# SCH_LD_project_2022-11-01.net
KiCad netlist of a schematic drawn in EasyEDA
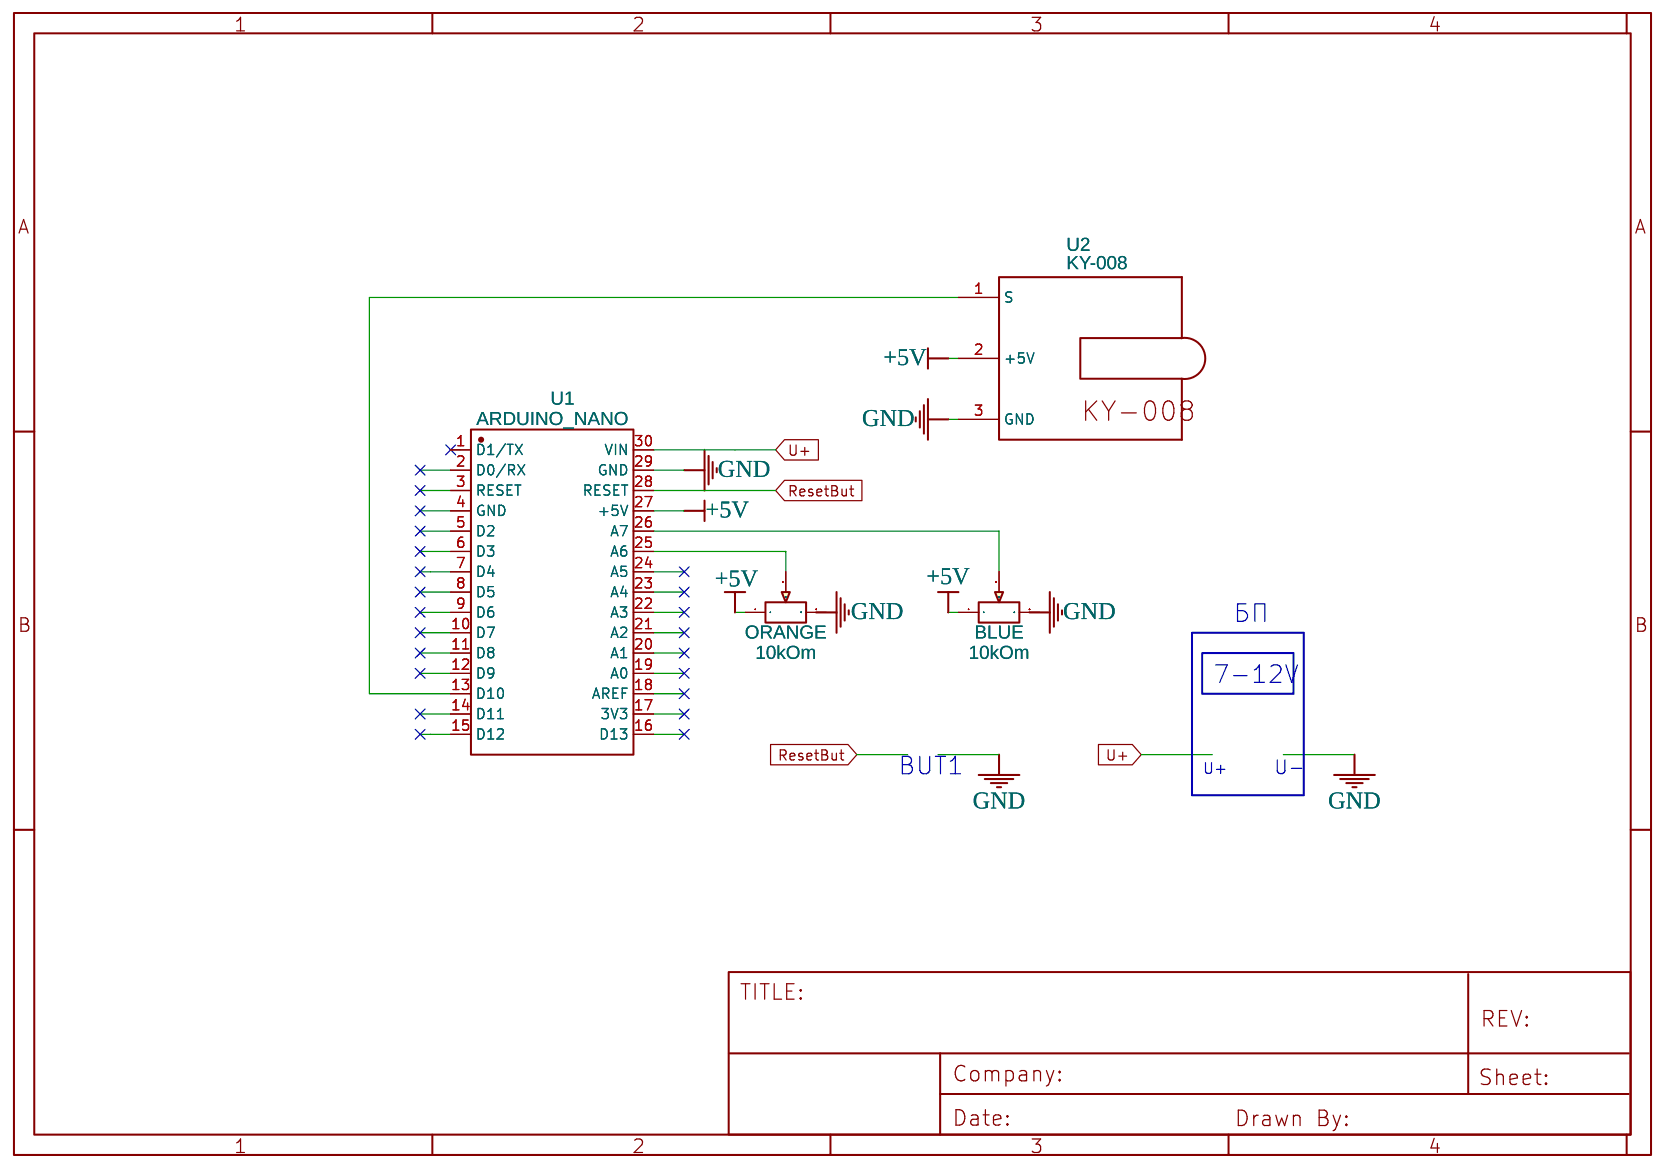
[diagram p0: schematic sheet]

(export (version "E")
  (design (tool "Eeschema 10.0.6"))
  (components
    (comp (ref "BLUE") (value "10kOm") (libsource (lib "") (part "R_3386P_EU")))
    (comp (ref "ORANGE") (value "10kOm") (libsource (lib "") (part "R_3386P_EU_1")))
    (comp (ref "U1")
      (value "ARDUINO_NANO")
      (fields (field (name "BOM_Supplier Part") "C9900017879"))
      (libsource (lib "") (part "ARDUINO_NANO"))
    )
    (comp (ref "U2") (value "KY-008") (libsource (lib "") (part "KY-008")))
  )
  (nets
    (net (code "1") (name "+5V") (class "Default")
      (node (ref "BLUE") (pin "1") (pinfunction "1_1") (pintype "input"))
      (node (ref "ORANGE") (pin "1") (pinfunction "1_1") (pintype "input"))
      (node (ref "U1") (pin "27") (pinfunction "+5V_27") (pintype "unspecified"))
      (node (ref "U2") (pin "2") (pinfunction "+5V_2") (pintype "unspecified"))
    )
    (net (code "2") (name "GND") (class "Default")
      (node (ref "BLUE") (pin "3") (pinfunction "3_3") (pintype "input"))
      (node (ref "ORANGE") (pin "3") (pinfunction "3_3") (pintype "input"))
      (node (ref "U1") (pin "29") (pinfunction "GND_29") (pintype "unspecified"))
      (node (ref "U2") (pin "3") (pinfunction "GND_3") (pintype "unspecified"))
    )
    (net (code "3") (name "Net-(U1-A6)") (class "Default")
      (node (ref "ORANGE") (pin "2") (pinfunction "2_2") (pintype "input"))
      (node (ref "U1") (pin "25") (pinfunction "A6_25") (pintype "unspecified"))
    )
    (net (code "4") (name "Net-(U1-A7)") (class "Default")
      (node (ref "BLUE") (pin "2") (pinfunction "2_2") (pintype "input"))
      (node (ref "U1") (pin "26") (pinfunction "A7_26") (pintype "unspecified"))
    )
    (net (code "5") (name "Net-(U1-D10)") (class "Default")
      (node (ref "U1") (pin "13") (pinfunction "D10_13") (pintype "unspecified"))
      (node (ref "U2") (pin "1") (pinfunction "S_1") (pintype "unspecified"))
    )
    (net (code "6") (name "ResetBut") (class "Default")
      (node (ref "U1") (pin "28") (pinfunction "RESET_28") (pintype "unspecified"))
    )
    (net (code "7") (name "U+") (class "Default")
      (node (ref "U1") (pin "30") (pinfunction "VIN_30") (pintype "unspecified"))
    )
    (net (code "8") (name "unconnected-(U1-3V3-Pad17)") (class "Default")
      (node (ref "U1") (pin "17") (pinfunction "3V3_17") (pintype "unspecified+no_connect"))
    )
    (net (code "9") (name "unconnected-(U1-A0-Pad19)") (class "Default")
      (node (ref "U1") (pin "19") (pinfunction "A0_19") (pintype "unspecified+no_connect"))
    )
    (net (code "10") (name "unconnected-(U1-A1-Pad20)") (class "Default")
      (node (ref "U1") (pin "20") (pinfunction "A1_20") (pintype "unspecified+no_connect"))
    )
    (net (code "11") (name "unconnected-(U1-A2-Pad21)") (class "Default")
      (node (ref "U1") (pin "21") (pinfunction "A2_21") (pintype "unspecified+no_connect"))
    )
    (net (code "12") (name "unconnected-(U1-A3-Pad22)") (class "Default")
      (node (ref "U1") (pin "22") (pinfunction "A3_22") (pintype "unspecified+no_connect"))
    )
    (net (code "13") (name "unconnected-(U1-A4-Pad23)") (class "Default")
      (node (ref "U1") (pin "23") (pinfunction "A4_23") (pintype "unspecified+no_connect"))
    )
    (net (code "14") (name "unconnected-(U1-A5-Pad24)") (class "Default")
      (node (ref "U1") (pin "24") (pinfunction "A5_24") (pintype "unspecified+no_connect"))
    )
    (net (code "15") (name "unconnected-(U1-AREF-Pad18)") (class "Default")
      (node (ref "U1") (pin "18") (pinfunction "AREF_18") (pintype "unspecified+no_connect"))
    )
    (net (code "16") (name "unconnected-(U1-D0{slash}RX-Pad2)") (class "Default")
      (node (ref "U1") (pin "2") (pinfunction "D0/RX_2") (pintype "unspecified+no_connect"))
    )
    (net (code "17") (name "unconnected-(U1-D1{slash}TX-Pad1)") (class "Default")
      (node (ref "U1") (pin "1") (pinfunction "D1/TX_1") (pintype "unspecified+no_connect"))
    )
    (net (code "18") (name "unconnected-(U1-D2-Pad5)") (class "Default")
      (node (ref "U1") (pin "5") (pinfunction "D2_5") (pintype "unspecified+no_connect"))
    )
    (net (code "19") (name "unconnected-(U1-D3-Pad6)") (class "Default")
      (node (ref "U1") (pin "6") (pinfunction "D3_6") (pintype "unspecified+no_connect"))
    )
    (net (code "20") (name "unconnected-(U1-D4-Pad7)") (class "Default")
      (node (ref "U1") (pin "7") (pinfunction "D4_7") (pintype "unspecified+no_connect"))
    )
    (net (code "21") (name "unconnected-(U1-D5-Pad8)") (class "Default")
      (node (ref "U1") (pin "8") (pinfunction "D5_8") (pintype "unspecified+no_connect"))
    )
    (net (code "22") (name "unconnected-(U1-D6-Pad9)") (class "Default")
      (node (ref "U1") (pin "9") (pinfunction "D6_9") (pintype "unspecified+no_connect"))
    )
    (net (code "23") (name "unconnected-(U1-D7-Pad10)") (class "Default")
      (node (ref "U1") (pin "10") (pinfunction "D7_10") (pintype "unspecified+no_connect"))
    )
    (net (code "24") (name "unconnected-(U1-D8-Pad11)") (class "Default")
      (node (ref "U1") (pin "11") (pinfunction "D8_11") (pintype "unspecified+no_connect"))
    )
    (net (code "25") (name "unconnected-(U1-D9-Pad12)") (class "Default")
      (node (ref "U1") (pin "12") (pinfunction "D9_12") (pintype "unspecified+no_connect"))
    )
    (net (code "26") (name "unconnected-(U1-D11-Pad14)") (class "Default")
      (node (ref "U1") (pin "14") (pinfunction "D11_14") (pintype "unspecified+no_connect"))
    )
    (net (code "27") (name "unconnected-(U1-D12-Pad15)") (class "Default")
      (node (ref "U1") (pin "15") (pinfunction "D12_15") (pintype "unspecified+no_connect"))
    )
    (net (code "28") (name "unconnected-(U1-D13-Pad16)") (class "Default")
      (node (ref "U1") (pin "16") (pinfunction "D13_16") (pintype "unspecified+no_connect"))
    )
    (net (code "29") (name "unconnected-(U1-GND-Pad4)") (class "Default")
      (node (ref "U1") (pin "4") (pinfunction "GND_4") (pintype "unspecified+no_connect"))
    )
    (net (code "30") (name "unconnected-(U1-RESET-Pad3)") (class "Default")
      (node (ref "U1") (pin "3") (pinfunction "RESET_3") (pintype "unspecified+no_connect"))
    )
  )
)
